# brain1_v12.net
KiCad netlist of a schematic drawn in EAGLE
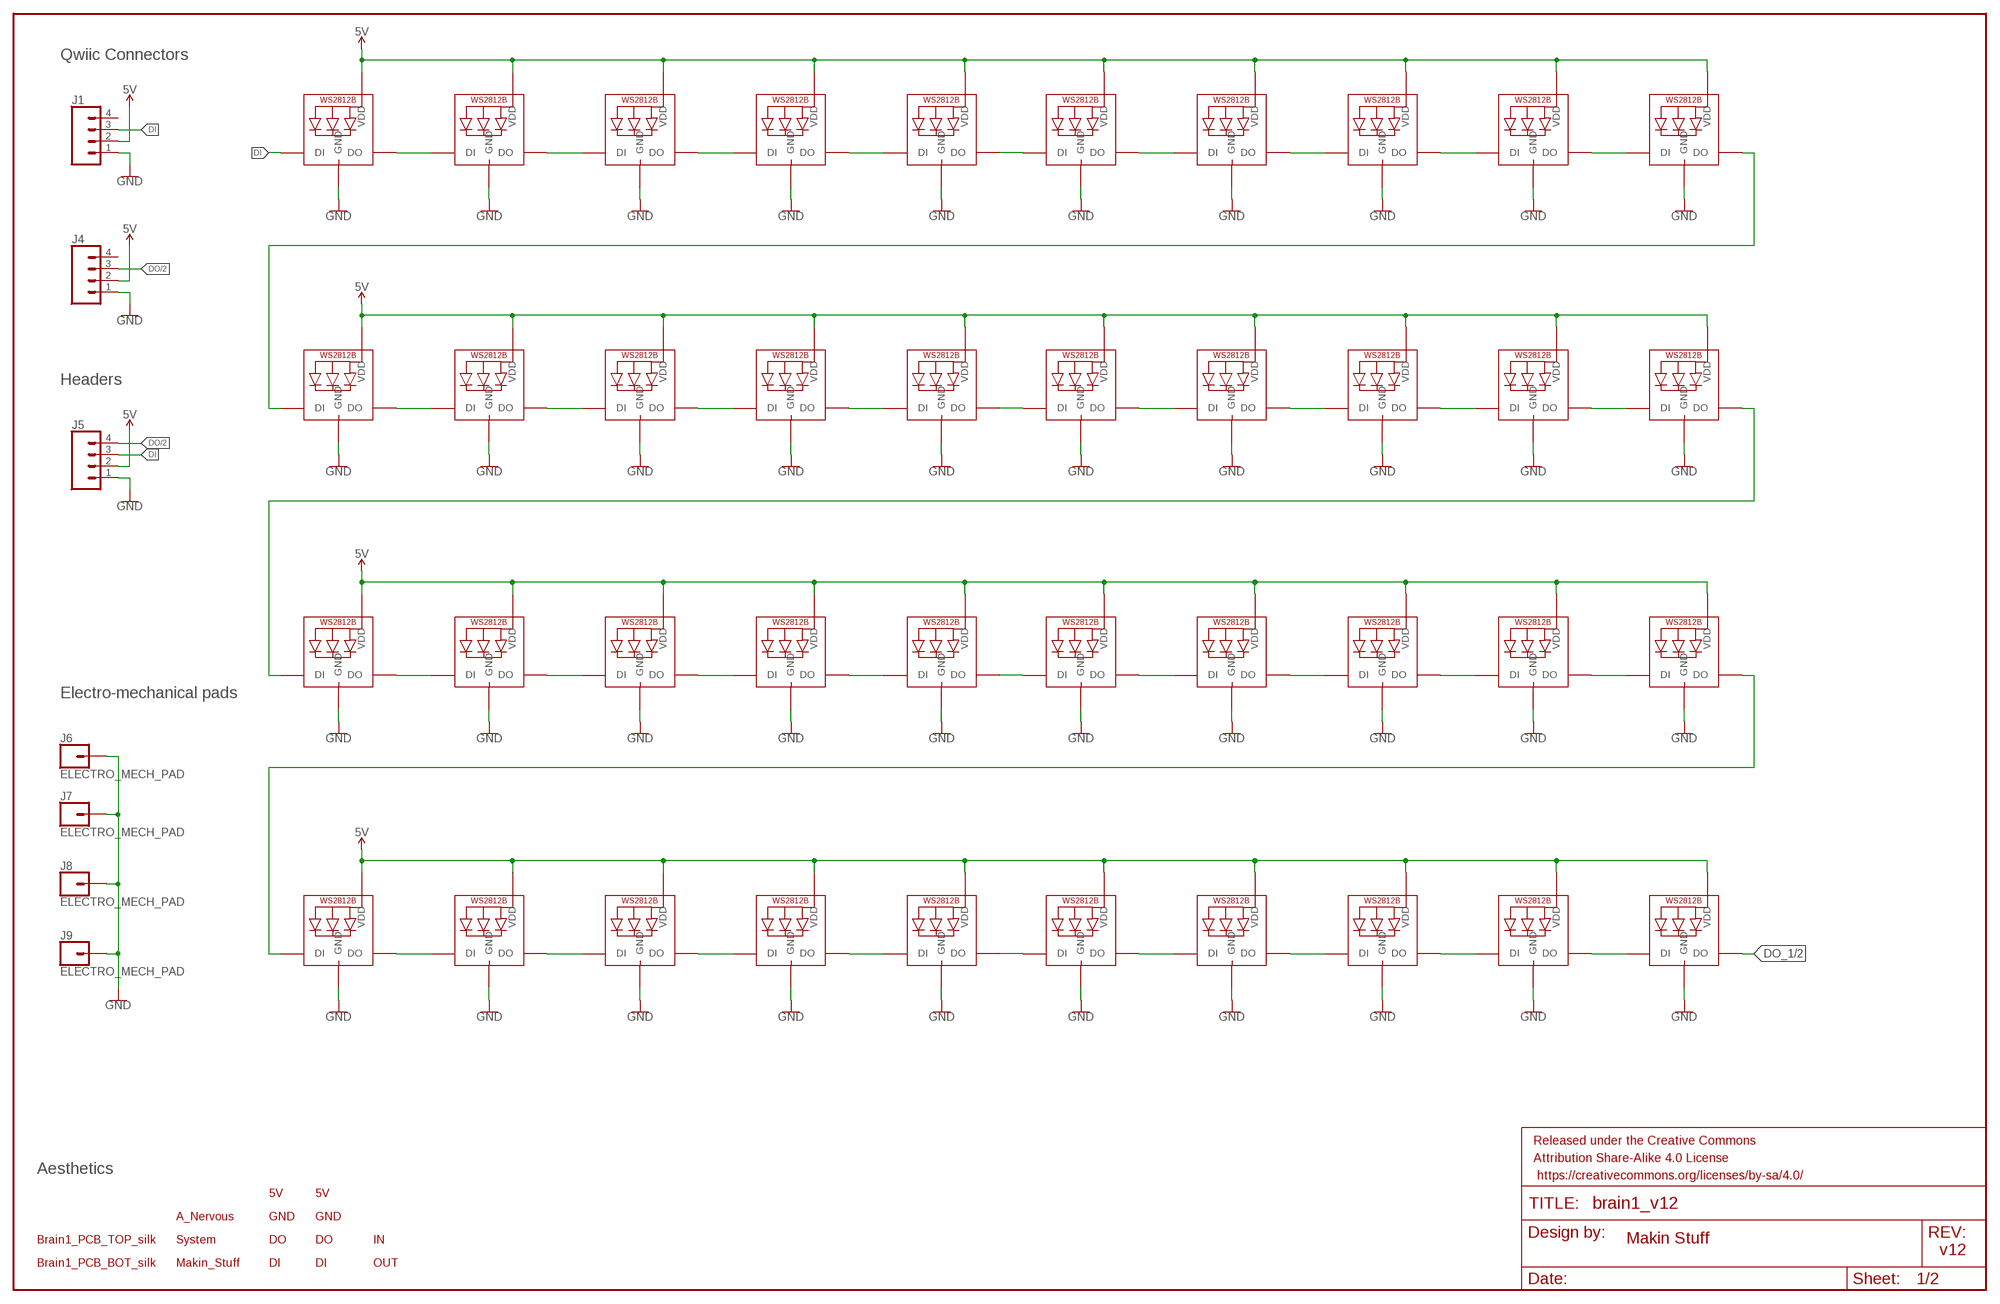
[diagram p0: schematic, sheet 1]
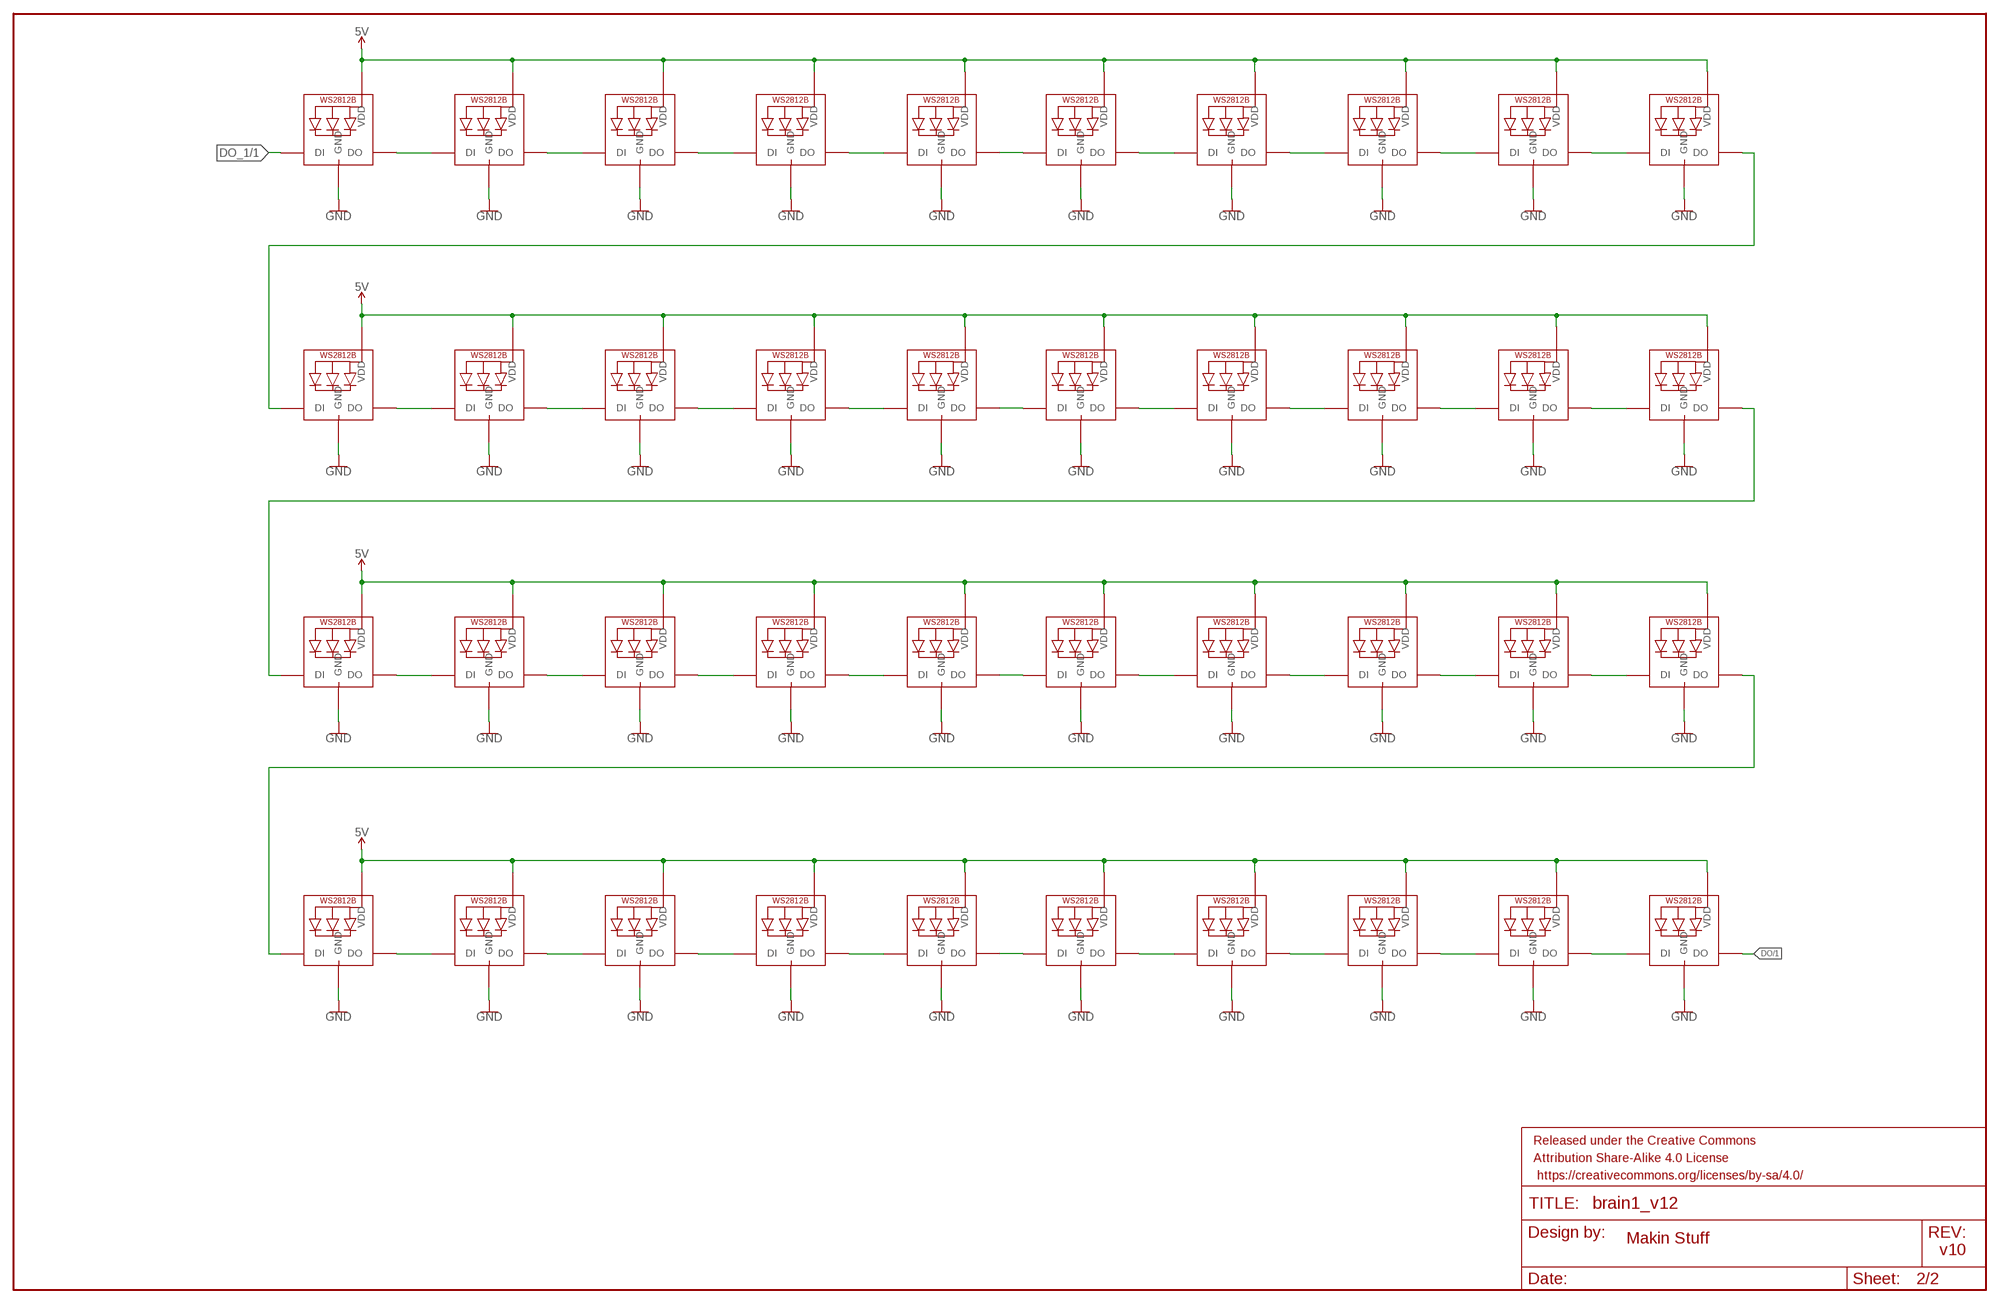
[diagram p1: schematic, sheet 2]

(export (version "E")
  (design (tool "Eeschema 10.0.6"))
  (components
    (comp (ref "FRAME1")
      (value "FRAME-LEDGER")
      (footprint "eagle-import:CREATIVE_COMMONS")
      (libsource (lib "eagle-import") (part "FRAME-LEDGER"))
    )
    (comp (ref "FRAME3")
      (value "FRAME-LEDGER")
      (footprint "eagle-import:CREATIVE_COMMONS")
      (libsource (lib "eagle-import") (part "FRAME-LEDGER"))
    )
    (comp (ref "LED41")
      (value "3.5X3.5_RGB_LED3.5X3.5")
      (footprint "eagle-import:3.5X3.5_RGB_LED")
      (libsource (lib "eagle-import") (part "3.5X3.5_RGB_LED3.5X3.5"))
    )
    (comp (ref "LED42")
      (value "3.5X3.5_RGB_LED3.5X3.5")
      (footprint "eagle-import:3.5X3.5_RGB_LED")
      (libsource (lib "eagle-import") (part "3.5X3.5_RGB_LED3.5X3.5"))
    )
    (comp (ref "LED43")
      (value "3.5X3.5_RGB_LED3.5X3.5")
      (footprint "eagle-import:3.5X3.5_RGB_LED")
      (libsource (lib "eagle-import") (part "3.5X3.5_RGB_LED3.5X3.5"))
    )
    (comp (ref "LED44")
      (value "3.5X3.5_RGB_LED3.5X3.5")
      (footprint "eagle-import:3.5X3.5_RGB_LED")
      (libsource (lib "eagle-import") (part "3.5X3.5_RGB_LED3.5X3.5"))
    )
    (comp (ref "LED45")
      (value "3.5X3.5_RGB_LED3.5X3.5")
      (footprint "eagle-import:3.5X3.5_RGB_LED")
      (libsource (lib "eagle-import") (part "3.5X3.5_RGB_LED3.5X3.5"))
    )
    (comp (ref "LED46")
      (value "3.5X3.5_RGB_LED3.5X3.5")
      (footprint "eagle-import:3.5X3.5_RGB_LED")
      (libsource (lib "eagle-import") (part "3.5X3.5_RGB_LED3.5X3.5"))
    )
    (comp (ref "LED47")
      (value "3.5X3.5_RGB_LED3.5X3.5")
      (footprint "eagle-import:3.5X3.5_RGB_LED")
      (libsource (lib "eagle-import") (part "3.5X3.5_RGB_LED3.5X3.5"))
    )
    (comp (ref "LED48")
      (value "3.5X3.5_RGB_LED3.5X3.5")
      (footprint "eagle-import:3.5X3.5_RGB_LED")
      (libsource (lib "eagle-import") (part "3.5X3.5_RGB_LED3.5X3.5"))
    )
    (comp (ref "LED49")
      (value "3.5X3.5_RGB_LED3.5X3.5")
      (footprint "eagle-import:3.5X3.5_RGB_LED")
      (libsource (lib "eagle-import") (part "3.5X3.5_RGB_LED3.5X3.5"))
    )
    (comp (ref "LED50")
      (value "3.5X3.5_RGB_LED3.5X3.5")
      (footprint "eagle-import:3.5X3.5_RGB_LED")
      (libsource (lib "eagle-import") (part "3.5X3.5_RGB_LED3.5X3.5"))
    )
    (comp (ref "LED51")
      (value "3.5X3.5_RGB_LED3.5X3.5")
      (footprint "eagle-import:3.5X3.5_RGB_LED")
      (libsource (lib "eagle-import") (part "3.5X3.5_RGB_LED3.5X3.5"))
    )
    (comp (ref "LED52")
      (value "3.5X3.5_RGB_LED3.5X3.5")
      (footprint "eagle-import:3.5X3.5_RGB_LED")
      (libsource (lib "eagle-import") (part "3.5X3.5_RGB_LED3.5X3.5"))
    )
    (comp (ref "LED53")
      (value "3.5X3.5_RGB_LED3.5X3.5")
      (footprint "eagle-import:3.5X3.5_RGB_LED")
      (libsource (lib "eagle-import") (part "3.5X3.5_RGB_LED3.5X3.5"))
    )
    (comp (ref "LED54")
      (value "3.5X3.5_RGB_LED3.5X3.5")
      (footprint "eagle-import:3.5X3.5_RGB_LED")
      (libsource (lib "eagle-import") (part "3.5X3.5_RGB_LED3.5X3.5"))
    )
    (comp (ref "LED55")
      (value "3.5X3.5_RGB_LED3.5X3.5")
      (footprint "eagle-import:3.5X3.5_RGB_LED")
      (libsource (lib "eagle-import") (part "3.5X3.5_RGB_LED3.5X3.5"))
    )
    (comp (ref "LED56")
      (value "3.5X3.5_RGB_LED3.5X3.5")
      (footprint "eagle-import:3.5X3.5_RGB_LED")
      (libsource (lib "eagle-import") (part "3.5X3.5_RGB_LED3.5X3.5"))
    )
    (comp (ref "LED57")
      (value "3.5X3.5_RGB_LED3.5X3.5")
      (footprint "eagle-import:3.5X3.5_RGB_LED")
      (libsource (lib "eagle-import") (part "3.5X3.5_RGB_LED3.5X3.5"))
    )
    (comp (ref "LED58")
      (value "3.5X3.5_RGB_LED3.5X3.5")
      (footprint "eagle-import:3.5X3.5_RGB_LED")
      (libsource (lib "eagle-import") (part "3.5X3.5_RGB_LED3.5X3.5"))
    )
    (comp (ref "LED59")
      (value "3.5X3.5_RGB_LED3.5X3.5")
      (footprint "eagle-import:3.5X3.5_RGB_LED")
      (libsource (lib "eagle-import") (part "3.5X3.5_RGB_LED3.5X3.5"))
    )
    (comp (ref "LED60")
      (value "3.5X3.5_RGB_LED3.5X3.5")
      (footprint "eagle-import:3.5X3.5_RGB_LED")
      (libsource (lib "eagle-import") (part "3.5X3.5_RGB_LED3.5X3.5"))
    )
    (comp (ref "LED61")
      (value "3.5X3.5_RGB_LED3.5X3.5")
      (footprint "eagle-import:3.5X3.5_RGB_LED")
      (libsource (lib "eagle-import") (part "3.5X3.5_RGB_LED3.5X3.5"))
    )
    (comp (ref "LED62")
      (value "3.5X3.5_RGB_LED3.5X3.5")
      (footprint "eagle-import:3.5X3.5_RGB_LED")
      (libsource (lib "eagle-import") (part "3.5X3.5_RGB_LED3.5X3.5"))
    )
    (comp (ref "LED63")
      (value "3.5X3.5_RGB_LED3.5X3.5")
      (footprint "eagle-import:3.5X3.5_RGB_LED")
      (libsource (lib "eagle-import") (part "3.5X3.5_RGB_LED3.5X3.5"))
    )
    (comp (ref "LED64")
      (value "3.5X3.5_RGB_LED3.5X3.5")
      (footprint "eagle-import:3.5X3.5_RGB_LED")
      (libsource (lib "eagle-import") (part "3.5X3.5_RGB_LED3.5X3.5"))
    )
    (comp (ref "LED65")
      (value "3.5X3.5_RGB_LED3.5X3.5")
      (footprint "eagle-import:3.5X3.5_RGB_LED")
      (libsource (lib "eagle-import") (part "3.5X3.5_RGB_LED3.5X3.5"))
    )
    (comp (ref "LED66")
      (value "3.5X3.5_RGB_LED3.5X3.5")
      (footprint "eagle-import:3.5X3.5_RGB_LED")
      (libsource (lib "eagle-import") (part "3.5X3.5_RGB_LED3.5X3.5"))
    )
    (comp (ref "LED67")
      (value "3.5X3.5_RGB_LED3.5X3.5")
      (footprint "eagle-import:3.5X3.5_RGB_LED")
      (libsource (lib "eagle-import") (part "3.5X3.5_RGB_LED3.5X3.5"))
    )
    (comp (ref "LED68")
      (value "3.5X3.5_RGB_LED3.5X3.5")
      (footprint "eagle-import:3.5X3.5_RGB_LED")
      (libsource (lib "eagle-import") (part "3.5X3.5_RGB_LED3.5X3.5"))
    )
    (comp (ref "LED69")
      (value "3.5X3.5_RGB_LED3.5X3.5")
      (footprint "eagle-import:3.5X3.5_RGB_LED")
      (libsource (lib "eagle-import") (part "3.5X3.5_RGB_LED3.5X3.5"))
    )
    (comp (ref "LED70")
      (value "3.5X3.5_RGB_LED3.5X3.5")
      (footprint "eagle-import:3.5X3.5_RGB_LED")
      (libsource (lib "eagle-import") (part "3.5X3.5_RGB_LED3.5X3.5"))
    )
    (comp (ref "LED71")
      (value "3.5X3.5_RGB_LED3.5X3.5")
      (footprint "eagle-import:3.5X3.5_RGB_LED")
      (libsource (lib "eagle-import") (part "3.5X3.5_RGB_LED3.5X3.5"))
    )
    (comp (ref "LED72")
      (value "3.5X3.5_RGB_LED3.5X3.5")
      (footprint "eagle-import:3.5X3.5_RGB_LED")
      (libsource (lib "eagle-import") (part "3.5X3.5_RGB_LED3.5X3.5"))
    )
    (comp (ref "LED73")
      (value "3.5X3.5_RGB_LED3.5X3.5")
      (footprint "eagle-import:3.5X3.5_RGB_LED")
      (libsource (lib "eagle-import") (part "3.5X3.5_RGB_LED3.5X3.5"))
    )
    (comp (ref "LED74")
      (value "3.5X3.5_RGB_LED3.5X3.5")
      (footprint "eagle-import:3.5X3.5_RGB_LED")
      (libsource (lib "eagle-import") (part "3.5X3.5_RGB_LED3.5X3.5"))
    )
    (comp (ref "LED75")
      (value "3.5X3.5_RGB_LED3.5X3.5")
      (footprint "eagle-import:3.5X3.5_RGB_LED")
      (libsource (lib "eagle-import") (part "3.5X3.5_RGB_LED3.5X3.5"))
    )
    (comp (ref "LED76")
      (value "3.5X3.5_RGB_LED3.5X3.5")
      (footprint "eagle-import:3.5X3.5_RGB_LED")
      (libsource (lib "eagle-import") (part "3.5X3.5_RGB_LED3.5X3.5"))
    )
    (comp (ref "LED77")
      (value "3.5X3.5_RGB_LED3.5X3.5")
      (footprint "eagle-import:3.5X3.5_RGB_LED")
      (libsource (lib "eagle-import") (part "3.5X3.5_RGB_LED3.5X3.5"))
    )
    (comp (ref "LED78")
      (value "3.5X3.5_RGB_LED3.5X3.5")
      (footprint "eagle-import:3.5X3.5_RGB_LED")
      (libsource (lib "eagle-import") (part "3.5X3.5_RGB_LED3.5X3.5"))
    )
    (comp (ref "LED79")
      (value "3.5X3.5_RGB_LED3.5X3.5")
      (footprint "eagle-import:3.5X3.5_RGB_LED")
      (libsource (lib "eagle-import") (part "3.5X3.5_RGB_LED3.5X3.5"))
    )
    (comp (ref "LED80")
      (value "3.5X3.5_RGB_LED3.5X3.5")
      (footprint "eagle-import:3.5X3.5_RGB_LED")
      (libsource (lib "eagle-import") (part "3.5X3.5_RGB_LED3.5X3.5"))
    )
    (comp (ref "FRAME2")
      (value "FRAME-LEDGER")
      (footprint "eagle-import:CREATIVE_COMMONS")
      (libsource (lib "eagle-import") (part "FRAME-LEDGER"))
    )
    (comp (ref "J1")
      (value "CONN_04SMD3")
      (footprint "eagle-import:JST04_1MM_RA")
      (libsource (lib "eagle-import") (part "CONN_04SMD3"))
    )
    (comp (ref "J4")
      (value "CONN_04SMD3")
      (footprint "eagle-import:JST04_1MM_RA")
      (libsource (lib "eagle-import") (part "CONN_04SMD3"))
    )
    (comp (ref "J5")
      (value "CONN_041X04_NO_SILK_NO_POP")
      (footprint "eagle-import:1X04_NO_SILK")
      (libsource (lib "eagle-import") (part "CONN_041X04_NO_SILK_NO_POP"))
    )
    (comp (ref "J6")
      (value "ELECTRO_MECH_PAD")
      (footprint "eagle-import:5X3_SOLDER_PAD")
      (libsource (lib "eagle-import") (part "ELECTRO_MECH_PAD"))
    )
    (comp (ref "J7")
      (value "ELECTRO_MECH_PAD")
      (footprint "eagle-import:5X3_SOLDER_PAD")
      (libsource (lib "eagle-import") (part "ELECTRO_MECH_PAD"))
    )
    (comp (ref "J8")
      (value "ELECTRO_MECH_PAD")
      (footprint "eagle-import:5X3_SOLDER_PAD")
      (libsource (lib "eagle-import") (part "ELECTRO_MECH_PAD"))
    )
    (comp (ref "J9")
      (value "ELECTRO_MECH_PAD")
      (footprint "eagle-import:5X3_SOLDER_PAD")
      (libsource (lib "eagle-import") (part "ELECTRO_MECH_PAD"))
    )
    (comp (ref "LED1")
      (value "3.5X3.5_RGB_LED3.5X3.5")
      (footprint "eagle-import:3.5X3.5_RGB_LED")
      (libsource (lib "eagle-import") (part "3.5X3.5_RGB_LED3.5X3.5"))
    )
    (comp (ref "LED2")
      (value "3.5X3.5_RGB_LED3.5X3.5")
      (footprint "eagle-import:3.5X3.5_RGB_LED")
      (libsource (lib "eagle-import") (part "3.5X3.5_RGB_LED3.5X3.5"))
    )
    (comp (ref "LED3")
      (value "3.5X3.5_RGB_LED3.5X3.5")
      (footprint "eagle-import:3.5X3.5_RGB_LED")
      (libsource (lib "eagle-import") (part "3.5X3.5_RGB_LED3.5X3.5"))
    )
    (comp (ref "LED4")
      (value "3.5X3.5_RGB_LED3.5X3.5")
      (footprint "eagle-import:3.5X3.5_RGB_LED")
      (libsource (lib "eagle-import") (part "3.5X3.5_RGB_LED3.5X3.5"))
    )
    (comp (ref "LED5")
      (value "3.5X3.5_RGB_LED3.5X3.5")
      (footprint "eagle-import:3.5X3.5_RGB_LED")
      (libsource (lib "eagle-import") (part "3.5X3.5_RGB_LED3.5X3.5"))
    )
    (comp (ref "LED6")
      (value "3.5X3.5_RGB_LED3.5X3.5")
      (footprint "eagle-import:3.5X3.5_RGB_LED")
      (libsource (lib "eagle-import") (part "3.5X3.5_RGB_LED3.5X3.5"))
    )
    (comp (ref "LED7")
      (value "3.5X3.5_RGB_LED3.5X3.5")
      (footprint "eagle-import:3.5X3.5_RGB_LED")
      (libsource (lib "eagle-import") (part "3.5X3.5_RGB_LED3.5X3.5"))
    )
    (comp (ref "LED8")
      (value "3.5X3.5_RGB_LED3.5X3.5")
      (footprint "eagle-import:3.5X3.5_RGB_LED")
      (libsource (lib "eagle-import") (part "3.5X3.5_RGB_LED3.5X3.5"))
    )
    (comp (ref "LED9")
      (value "3.5X3.5_RGB_LED3.5X3.5")
      (footprint "eagle-import:3.5X3.5_RGB_LED")
      (libsource (lib "eagle-import") (part "3.5X3.5_RGB_LED3.5X3.5"))
    )
    (comp (ref "LED10")
      (value "3.5X3.5_RGB_LED3.5X3.5")
      (footprint "eagle-import:3.5X3.5_RGB_LED")
      (libsource (lib "eagle-import") (part "3.5X3.5_RGB_LED3.5X3.5"))
    )
    (comp (ref "LED11")
      (value "3.5X3.5_RGB_LED3.5X3.5")
      (footprint "eagle-import:3.5X3.5_RGB_LED")
      (libsource (lib "eagle-import") (part "3.5X3.5_RGB_LED3.5X3.5"))
    )
    (comp (ref "LED12")
      (value "3.5X3.5_RGB_LED3.5X3.5")
      (footprint "eagle-import:3.5X3.5_RGB_LED")
      (libsource (lib "eagle-import") (part "3.5X3.5_RGB_LED3.5X3.5"))
    )
    (comp (ref "LED13")
      (value "3.5X3.5_RGB_LED3.5X3.5")
      (footprint "eagle-import:3.5X3.5_RGB_LED")
      (libsource (lib "eagle-import") (part "3.5X3.5_RGB_LED3.5X3.5"))
    )
    (comp (ref "LED14")
      (value "3.5X3.5_RGB_LED3.5X3.5")
      (footprint "eagle-import:3.5X3.5_RGB_LED")
      (libsource (lib "eagle-import") (part "3.5X3.5_RGB_LED3.5X3.5"))
    )
    (comp (ref "LED15")
      (value "3.5X3.5_RGB_LED3.5X3.5")
      (footprint "eagle-import:3.5X3.5_RGB_LED")
      (libsource (lib "eagle-import") (part "3.5X3.5_RGB_LED3.5X3.5"))
    )
    (comp (ref "LED16")
      (value "3.5X3.5_RGB_LED3.5X3.5")
      (footprint "eagle-import:3.5X3.5_RGB_LED")
      (libsource (lib "eagle-import") (part "3.5X3.5_RGB_LED3.5X3.5"))
    )
    (comp (ref "LED17")
      (value "3.5X3.5_RGB_LED3.5X3.5")
      (footprint "eagle-import:3.5X3.5_RGB_LED")
      (libsource (lib "eagle-import") (part "3.5X3.5_RGB_LED3.5X3.5"))
    )
    (comp (ref "LED18")
      (value "3.5X3.5_RGB_LED3.5X3.5")
      (footprint "eagle-import:3.5X3.5_RGB_LED")
      (libsource (lib "eagle-import") (part "3.5X3.5_RGB_LED3.5X3.5"))
    )
    (comp (ref "LED19")
      (value "3.5X3.5_RGB_LED3.5X3.5")
      (footprint "eagle-import:3.5X3.5_RGB_LED")
      (libsource (lib "eagle-import") (part "3.5X3.5_RGB_LED3.5X3.5"))
    )
    (comp (ref "LED20")
      (value "3.5X3.5_RGB_LED3.5X3.5")
      (footprint "eagle-import:3.5X3.5_RGB_LED")
      (libsource (lib "eagle-import") (part "3.5X3.5_RGB_LED3.5X3.5"))
    )
    (comp (ref "LED21")
      (value "3.5X3.5_RGB_LED3.5X3.5")
      (footprint "eagle-import:3.5X3.5_RGB_LED")
      (libsource (lib "eagle-import") (part "3.5X3.5_RGB_LED3.5X3.5"))
    )
    (comp (ref "LED22")
      (value "3.5X3.5_RGB_LED3.5X3.5")
      (footprint "eagle-import:3.5X3.5_RGB_LED")
      (libsource (lib "eagle-import") (part "3.5X3.5_RGB_LED3.5X3.5"))
    )
    (comp (ref "LED23")
      (value "3.5X3.5_RGB_LED3.5X3.5")
      (footprint "eagle-import:3.5X3.5_RGB_LED")
      (libsource (lib "eagle-import") (part "3.5X3.5_RGB_LED3.5X3.5"))
    )
    (comp (ref "LED24")
      (value "3.5X3.5_RGB_LED3.5X3.5")
      (footprint "eagle-import:3.5X3.5_RGB_LED")
      (libsource (lib "eagle-import") (part "3.5X3.5_RGB_LED3.5X3.5"))
    )
    (comp (ref "LED25")
      (value "3.5X3.5_RGB_LED3.5X3.5")
      (footprint "eagle-import:3.5X3.5_RGB_LED")
      (libsource (lib "eagle-import") (part "3.5X3.5_RGB_LED3.5X3.5"))
    )
    (comp (ref "LED26")
      (value "3.5X3.5_RGB_LED3.5X3.5")
      (footprint "eagle-import:3.5X3.5_RGB_LED")
      (libsource (lib "eagle-import") (part "3.5X3.5_RGB_LED3.5X3.5"))
    )
    (comp (ref "LED27")
      (value "3.5X3.5_RGB_LED3.5X3.5")
      (footprint "eagle-import:3.5X3.5_RGB_LED")
      (libsource (lib "eagle-import") (part "3.5X3.5_RGB_LED3.5X3.5"))
    )
    (comp (ref "LED28")
      (value "3.5X3.5_RGB_LED3.5X3.5")
      (footprint "eagle-import:3.5X3.5_RGB_LED")
      (libsource (lib "eagle-import") (part "3.5X3.5_RGB_LED3.5X3.5"))
    )
    (comp (ref "LED29")
      (value "3.5X3.5_RGB_LED3.5X3.5")
      (footprint "eagle-import:3.5X3.5_RGB_LED")
      (libsource (lib "eagle-import") (part "3.5X3.5_RGB_LED3.5X3.5"))
    )
    (comp (ref "LED30")
      (value "3.5X3.5_RGB_LED3.5X3.5")
      (footprint "eagle-import:3.5X3.5_RGB_LED")
      (libsource (lib "eagle-import") (part "3.5X3.5_RGB_LED3.5X3.5"))
    )
    (comp (ref "LED31")
      (value "3.5X3.5_RGB_LED3.5X3.5")
      (footprint "eagle-import:3.5X3.5_RGB_LED")
      (libsource (lib "eagle-import") (part "3.5X3.5_RGB_LED3.5X3.5"))
    )
    (comp (ref "LED32")
      (value "3.5X3.5_RGB_LED3.5X3.5")
      (footprint "eagle-import:3.5X3.5_RGB_LED")
      (libsource (lib "eagle-import") (part "3.5X3.5_RGB_LED3.5X3.5"))
    )
    (comp (ref "LED33")
      (value "3.5X3.5_RGB_LED3.5X3.5")
      (footprint "eagle-import:3.5X3.5_RGB_LED")
      (libsource (lib "eagle-import") (part "3.5X3.5_RGB_LED3.5X3.5"))
    )
    (comp (ref "LED34")
      (value "3.5X3.5_RGB_LED3.5X3.5")
      (footprint "eagle-import:3.5X3.5_RGB_LED")
      (libsource (lib "eagle-import") (part "3.5X3.5_RGB_LED3.5X3.5"))
    )
    (comp (ref "LED35")
      (value "3.5X3.5_RGB_LED3.5X3.5")
      (footprint "eagle-import:3.5X3.5_RGB_LED")
      (libsource (lib "eagle-import") (part "3.5X3.5_RGB_LED3.5X3.5"))
    )
    (comp (ref "LED36")
      (value "3.5X3.5_RGB_LED3.5X3.5")
      (footprint "eagle-import:3.5X3.5_RGB_LED")
      (libsource (lib "eagle-import") (part "3.5X3.5_RGB_LED3.5X3.5"))
    )
    (comp (ref "LED37")
      (value "3.5X3.5_RGB_LED3.5X3.5")
      (footprint "eagle-import:3.5X3.5_RGB_LED")
      (libsource (lib "eagle-import") (part "3.5X3.5_RGB_LED3.5X3.5"))
    )
    (comp (ref "LED38")
      (value "3.5X3.5_RGB_LED3.5X3.5")
      (footprint "eagle-import:3.5X3.5_RGB_LED")
      (libsource (lib "eagle-import") (part "3.5X3.5_RGB_LED3.5X3.5"))
    )
    (comp (ref "LED39")
      (value "3.5X3.5_RGB_LED3.5X3.5")
      (footprint "eagle-import:3.5X3.5_RGB_LED")
      (libsource (lib "eagle-import") (part "3.5X3.5_RGB_LED3.5X3.5"))
    )
    (comp (ref "LED40")
      (value "3.5X3.5_RGB_LED3.5X3.5")
      (footprint "eagle-import:3.5X3.5_RGB_LED")
      (libsource (lib "eagle-import") (part "3.5X3.5_RGB_LED3.5X3.5"))
    )
    (comp (ref "U$1")
      (value "BRAIN1_PCB_BOT_SILK")
      (footprint "eagle-import:BRAIN1_PCB_BOT_SILK")
      (libsource (lib "eagle-import") (part "BRAIN1_PCB_BOT_SILK"))
    )
    (comp (ref "U$2")
      (value "BRAIN1_PCB_TOP_SILK")
      (footprint "eagle-import:BRAIN1_PCB_TOP_SILK")
      (libsource (lib "eagle-import") (part "BRAIN1_PCB_TOP_SILK"))
    )
    (comp (ref "U$3")
      (value "MAKIN_STUFF2")
      (footprint "eagle-import:MAKIN_STUFF2")
      (libsource (lib "eagle-import") (part "MAKIN_STUFF2"))
    )
    (comp (ref "U$4")
      (value "A_NERVOUS0")
      (footprint "eagle-import:A_NERVOUS0")
      (libsource (lib "eagle-import") (part "A_NERVOUS0"))
    )
    (comp (ref "U$5")
      (value "SYSTEM1")
      (footprint "eagle-import:SYSTEM1")
      (libsource (lib "eagle-import") (part "SYSTEM1"))
    )
    (comp (ref "U$6")
      (value "5V1")
      (footprint "eagle-import:5V1")
      (libsource (lib "eagle-import") (part "buzzard_labels (6)_5V1"))
    )
    (comp (ref "U$7")
      (value "GND0")
      (footprint "eagle-import:GND0")
      (libsource (lib "eagle-import") (part "buzzard_labels (6)_GND0"))
    )
    (comp (ref "U$8")
      (value "DO3")
      (footprint "eagle-import:DO3")
      (libsource (lib "eagle-import") (part "buzzard_labels (6)_DO3"))
    )
    (comp (ref "U$9")
      (value "DI0")
      (footprint "eagle-import:DI0")
      (libsource (lib "eagle-import") (part "buzzard_labels (7)_DI0"))
    )
    (comp (ref "U$10")
      (value "5V1")
      (footprint "eagle-import:5V1")
      (libsource (lib "eagle-import") (part "5V1"))
    )
    (comp (ref "U$11")
      (value "GND0")
      (footprint "eagle-import:GND0")
      (libsource (lib "eagle-import") (part "GND0"))
    )
    (comp (ref "U$12")
      (value "DI0")
      (footprint "eagle-import:DI0")
      (libsource (lib "eagle-import") (part "DI0"))
    )
    (comp (ref "U$13")
      (value "DO3")
      (footprint "eagle-import:DO3")
      (libsource (lib "eagle-import") (part "DO3"))
    )
    (comp (ref "U$14")
      (value "IN0")
      (footprint "eagle-import:IN0")
      (libsource (lib "eagle-import") (part "IN0"))
    )
    (comp (ref "U$15")
      (value "OUT1")
      (footprint "eagle-import:OUT1")
      (libsource (lib "eagle-import") (part "OUT1"))
    )
  )
  (nets
    (net (code "1") (name "5V") (class "Default")
      (node (ref "J1") (pin "2") (pinfunction "2_2") (pintype "passive"))
      (node (ref "J4") (pin "2") (pinfunction "2_2") (pintype "passive"))
      (node (ref "J5") (pin "2") (pinfunction "2_2") (pintype "passive"))
      (node (ref "LED1") (pin "4") (pinfunction "VDD_4") (pintype "power_in"))
      (node (ref "LED10") (pin "4") (pinfunction "VDD_4") (pintype "power_in"))
      (node (ref "LED11") (pin "4") (pinfunction "VDD_4") (pintype "power_in"))
      (node (ref "LED12") (pin "4") (pinfunction "VDD_4") (pintype "power_in"))
      (node (ref "LED13") (pin "4") (pinfunction "VDD_4") (pintype "power_in"))
      (node (ref "LED14") (pin "4") (pinfunction "VDD_4") (pintype "power_in"))
      (node (ref "LED15") (pin "4") (pinfunction "VDD_4") (pintype "power_in"))
      (node (ref "LED16") (pin "4") (pinfunction "VDD_4") (pintype "power_in"))
      (node (ref "LED17") (pin "4") (pinfunction "VDD_4") (pintype "power_in"))
      (node (ref "LED18") (pin "4") (pinfunction "VDD_4") (pintype "power_in"))
      (node (ref "LED19") (pin "4") (pinfunction "VDD_4") (pintype "power_in"))
      (node (ref "LED2") (pin "4") (pinfunction "VDD_4") (pintype "power_in"))
      (node (ref "LED20") (pin "4") (pinfunction "VDD_4") (pintype "power_in"))
      (node (ref "LED21") (pin "4") (pinfunction "VDD_4") (pintype "power_in"))
      (node (ref "LED22") (pin "4") (pinfunction "VDD_4") (pintype "power_in"))
      (node (ref "LED23") (pin "4") (pinfunction "VDD_4") (pintype "power_in"))
      (node (ref "LED24") (pin "4") (pinfunction "VDD_4") (pintype "power_in"))
      (node (ref "LED25") (pin "4") (pinfunction "VDD_4") (pintype "power_in"))
      (node (ref "LED26") (pin "4") (pinfunction "VDD_4") (pintype "power_in"))
      (node (ref "LED27") (pin "4") (pinfunction "VDD_4") (pintype "power_in"))
      (node (ref "LED28") (pin "4") (pinfunction "VDD_4") (pintype "power_in"))
      (node (ref "LED29") (pin "4") (pinfunction "VDD_4") (pintype "power_in"))
      (node (ref "LED3") (pin "4") (pinfunction "VDD_4") (pintype "power_in"))
      (node (ref "LED30") (pin "4") (pinfunction "VDD_4") (pintype "power_in"))
      (node (ref "LED31") (pin "4") (pinfunction "VDD_4") (pintype "power_in"))
      (node (ref "LED32") (pin "4") (pinfunction "VDD_4") (pintype "power_in"))
      (node (ref "LED33") (pin "4") (pinfunction "VDD_4") (pintype "power_in"))
      (node (ref "LED34") (pin "4") (pinfunction "VDD_4") (pintype "power_in"))
      (node (ref "LED35") (pin "4") (pinfunction "VDD_4") (pintype "power_in"))
      (node (ref "LED36") (pin "4") (pinfunction "VDD_4") (pintype "power_in"))
      (node (ref "LED37") (pin "4") (pinfunction "VDD_4") (pintype "power_in"))
      (node (ref "LED38") (pin "4") (pinfunction "VDD_4") (pintype "power_in"))
      (node (ref "LED39") (pin "4") (pinfunction "VDD_4") (pintype "power_in"))
      (node (ref "LED4") (pin "4") (pinfunction "VDD_4") (pintype "power_in"))
      (node (ref "LED40") (pin "4") (pinfunction "VDD_4") (pintype "power_in"))
      (node (ref "LED41") (pin "4") (pinfunction "VDD_4") (pintype "power_in"))
      (node (ref "LED42") (pin "4") (pinfunction "VDD_4") (pintype "power_in"))
      (node (ref "LED43") (pin "4") (pinfunction "VDD_4") (pintype "power_in"))
      (node (ref "LED44") (pin "4") (pinfunction "VDD_4") (pintype "power_in"))
      (node (ref "LED45") (pin "4") (pinfunction "VDD_4") (pintype "power_in"))
      (node (ref "LED46") (pin "4") (pinfunction "VDD_4") (pintype "power_in"))
      (node (ref "LED47") (pin "4") (pinfunction "VDD_4") (pintype "power_in"))
      (node (ref "LED48") (pin "4") (pinfunction "VDD_4") (pintype "power_in"))
      (node (ref "LED49") (pin "4") (pinfunction "VDD_4") (pintype "power_in"))
      (node (ref "LED5") (pin "4") (pinfunction "VDD_4") (pintype "power_in"))
      (node (ref "LED50") (pin "4") (pinfunction "VDD_4") (pintype "power_in"))
      (node (ref "LED51") (pin "4") (pinfunction "VDD_4") (pintype "power_in"))
      (node (ref "LED52") (pin "4") (pinfunction "VDD_4") (pintype "power_in"))
      (node (ref "LED53") (pin "4") (pinfunction "VDD_4") (pintype "power_in"))
      (node (ref "LED54") (pin "4") (pinfunction "VDD_4") (pintype "power_in"))
      (node (ref "LED55") (pin "4") (pinfunction "VDD_4") (pintype "power_in"))
      (node (ref "LED56") (pin "4") (pinfunction "VDD_4") (pintype "power_in"))
      (node (ref "LED57") (pin "4") (pinfunction "VDD_4") (pintype "power_in"))
      (node (ref "LED58") (pin "4") (pinfunction "VDD_4") (pintype "power_in"))
      (node (ref "LED59") (pin "4") (pinfunction "VDD_4") (pintype "power_in"))
      (node (ref "LED6") (pin "4") (pinfunction "VDD_4") (pintype "power_in"))
      (node (ref "LED60") (pin "4") (pinfunction "VDD_4") (pintype "power_in"))
      (node (ref "LED61") (pin "4") (pinfunction "VDD_4") (pintype "power_in"))
      (node (ref "LED62") (pin "4") (pinfunction "VDD_4") (pintype "power_in"))
      (node (ref "LED63") (pin "4") (pinfunction "VDD_4") (pintype "power_in"))
      (node (ref "LED64") (pin "4") (pinfunction "VDD_4") (pintype "power_in"))
      (node (ref "LED65") (pin "4") (pinfunction "VDD_4") (pintype "power_in"))
      (node (ref "LED66") (pin "4") (pinfunction "VDD_4") (pintype "power_in"))
      (node (ref "LED67") (pin "4") (pinfunction "VDD_4") (pintype "power_in"))
      (node (ref "LED68") (pin "4") (pinfunction "VDD_4") (pintype "power_in"))
      (node (ref "LED69") (pin "4") (pinfunction "VDD_4") (pintype "power_in"))
      (node (ref "LED7") (pin "4") (pinfunction "VDD_4") (pintype "power_in"))
      (node (ref "LED70") (pin "4") (pinfunction "VDD_4") (pintype "power_in"))
      (node (ref "LED71") (pin "4") (pinfunction "VDD_4") (pintype "power_in"))
      (node (ref "LED72") (pin "4") (pinfunction "VDD_4") (pintype "power_in"))
      (node (ref "LED73") (pin "4") (pinfunction "VDD_4") (pintype "power_in"))
      (node (ref "LED74") (pin "4") (pinfunction "VDD_4") (pintype "power_in"))
      (node (ref "LED75") (pin "4") (pinfunction "VDD_4") (pintype "power_in"))
      (node (ref "LED76") (pin "4") (pinfunction "VDD_4") (pintype "power_in"))
      (node (ref "LED77") (pin "4") (pinfunction "VDD_4") (pintype "power_in"))
      (node (ref "LED78") (pin "4") (pinfunction "VDD_4") (pintype "power_in"))
      (node (ref "LED79") (pin "4") (pinfunction "VDD_4") (pintype "power_in"))
      (node (ref "LED8") (pin "4") (pinfunction "VDD_4") (pintype "power_in"))
      (node (ref "LED80") (pin "4") (pinfunction "VDD_4") (pintype "power_in"))
      (node (ref "LED9") (pin "4") (pinfunction "VDD_4") (pintype "power_in"))
    )
    (net (code "2") (name "DI") (class "Default")
      (node (ref "J1") (pin "3") (pinfunction "3_3") (pintype "passive"))
      (node (ref "J5") (pin "3") (pinfunction "3_3") (pintype "passive"))
      (node (ref "LED1") (pin "3") (pinfunction "DI_3") (pintype "input"))
    )
    (net (code "3") (name "DO") (class "Default")
      (node (ref "J4") (pin "3") (pinfunction "3_3") (pintype "passive"))
      (node (ref "J5") (pin "4") (pinfunction "4_4") (pintype "passive"))
      (node (ref "LED80") (pin "1") (pinfunction "DO_1") (pintype "output"))
    )
    (net (code "4") (name "DO_1") (class "Default")
      (node (ref "LED40") (pin "1") (pinfunction "DO_1") (pintype "output"))
      (node (ref "LED41") (pin "3") (pinfunction "DI_3") (pintype "input"))
    )
    (net (code "5") (name "GND") (class "Default")
      (node (ref "J1") (pin "1") (pinfunction "1_1") (pintype "passive"))
      (node (ref "J4") (pin "1") (pinfunction "1_1") (pintype "passive"))
      (node (ref "J5") (pin "1") (pinfunction "1_1") (pintype "passive"))
      (node (ref "J6") (pin "P$1") (pinfunction "1_P$1") (pintype "passive"))
      (node (ref "J7") (pin "P$1") (pinfunction "1_P$1") (pintype "passive"))
      (node (ref "J8") (pin "P$1") (pinfunction "1_P$1") (pintype "passive"))
      (node (ref "J9") (pin "P$1") (pinfunction "1_P$1") (pintype "passive"))
      (node (ref "LED1") (pin "2") (pinfunction "GND_2") (pintype "power_in"))
      (node (ref "LED10") (pin "2") (pinfunction "GND_2") (pintype "power_in"))
      (node (ref "LED11") (pin "2") (pinfunction "GND_2") (pintype "power_in"))
      (node (ref "LED12") (pin "2") (pinfunction "GND_2") (pintype "power_in"))
      (node (ref "LED13") (pin "2") (pinfunction "GND_2") (pintype "power_in"))
      (node (ref "LED14") (pin "2") (pinfunction "GND_2") (pintype "power_in"))
      (node (ref "LED15") (pin "2") (pinfunction "GND_2") (pintype "power_in"))
      (node (ref "LED16") (pin "2") (pinfunction "GND_2") (pintype "power_in"))
      (node (ref "LED17") (pin "2") (pinfunction "GND_2") (pintype "power_in"))
      (node (ref "LED18") (pin "2") (pinfunction "GND_2") (pintype "power_in"))
      (node (ref "LED19") (pin "2") (pinfunction "GND_2") (pintype "power_in"))
      (node (ref "LED2") (pin "2") (pinfunction "GND_2") (pintype "power_in"))
      (node (ref "LED20") (pin "2") (pinfunction "GND_2") (pintype "power_in"))
      (node (ref "LED21") (pin "2") (pinfunction "GND_2") (pintype "power_in"))
      (node (ref "LED22") (pin "2") (pinfunction "GND_2") (pintype "power_in"))
      (node (ref "LED23") (pin "2") (pinfunction "GND_2") (pintype "power_in"))
      (node (ref "LED24") (pin "2") (pinfunction "GND_2") (pintype "power_in"))
      (node (ref "LED25") (pin "2") (pinfunction "GND_2") (pintype "power_in"))
      (node (ref "LED26") (pin "2") (pinfunction "GND_2") (pintype "power_in"))
      (node (ref "LED27") (pin "2") (pinfunction "GND_2") (pintype "power_in"))
      (node (ref "LED28") (pin "2") (pinfunction "GND_2") (pintype "power_in"))
      (node (ref "LED29") (pin "2") (pinfunction "GND_2") (pintype "power_in"))
      (node (ref "LED3") (pin "2") (pinfunction "GND_2") (pintype "power_in"))
      (node (ref "LED30") (pin "2") (pinfunction "GND_2") (pintype "power_in"))
      (node (ref "LED31") (pin "2") (pinfunction "GND_2") (pintype "power_in"))
      (node (ref "LED32") (pin "2") (pinfunction "GND_2") (pintype "power_in"))
      (node (ref "LED33") (pin "2") (pinfunction "GND_2") (pintype "power_in"))
      (node (ref "LED34") (pin "2") (pinfunction "GND_2") (pintype "power_in"))
      (node (ref "LED35") (pin "2") (pinfunction "GND_2") (pintype "power_in"))
      (node (ref "LED36") (pin "2") (pinfunction "GND_2") (pintype "power_in"))
      (node (ref "LED37") (pin "2") (pinfunction "GND_2") (pintype "power_in"))
      (node (ref "LED38") (pin "2") (pinfunction "GND_2") (pintype "power_in"))
      (node (ref "LED39") (pin "2") (pinfunction "GND_2") (pintype "power_in"))
      (node (ref "LED4") (pin "2") (pinfunction "GND_2") (pintype "power_in"))
      (node (ref "LED40") (pin "2") (pinfunction "GND_2") (pintype "power_in"))
      (node (ref "LED41") (pin "2") (pinfunction "GND_2") (pintype "power_in"))
      (node (ref "LED42") (pin "2") (pinfunction "GND_2") (pintype "power_in"))
      (node (ref "LED43") (pin "2") (pinfunction "GND_2") (pintype "power_in"))
      (node (ref "LED44") (pin "2") (pinfunction "GND_2") (pintype "power_in"))
      (node (ref "LED45") (pin "2") (pinfunction "GND_2") (pintype "power_in"))
      (node (ref "LED46") (pin "2") (pinfunction "GND_2") (pintype "power_in"))
      (node (ref "LED47") (pin "2") (pinfunction "GND_2") (pintype "power_in"))
      (node (ref "LED48") (pin "2") (pinfunction "GND_2") (pintype "power_in"))
      (node (ref "LED49") (pin "2") (pinfunction "GND_2") (pintype "power_in"))
      (node (ref "LED5") (pin "2") (pinfunction "GND_2") (pintype "power_in"))
      (node (ref "LED50") (pin "2") (pinfunction "GND_2") (pintype "power_in"))
      (node (ref "LED51") (pin "2") (pinfunction "GND_2") (pintype "power_in"))
      (node (ref "LED52") (pin "2") (pinfunction "GND_2") (pintype "power_in"))
      (node (ref "LED53") (pin "2") (pinfunction "GND_2") (pintype "power_in"))
      (node (ref "LED54") (pin "2") (pinfunction "GND_2") (pintype "power_in"))
      (node (ref "LED55") (pin "2") (pinfunction "GND_2") (pintype "power_in"))
      (node (ref "LED56") (pin "2") (pinfunction "GND_2") (pintype "power_in"))
      (node (ref "LED57") (pin "2") (pinfunction "GND_2") (pintype "power_in"))
      (node (ref "LED58") (pin "2") (pinfunction "GND_2") (pintype "power_in"))
      (node (ref "LED59") (pin "2") (pinfunction "GND_2") (pintype "power_in"))
      (node (ref "LED6") (pin "2") (pinfunction "GND_2") (pintype "power_in"))
      (node (ref "LED60") (pin "2") (pinfunction "GND_2") (pintype "power_in"))
      (node (ref "LED61") (pin "2") (pinfunction "GND_2") (pintype "power_in"))
      (node (ref "LED62") (pin "2") (pinfunction "GND_2") (pintype "power_in"))
      (node (ref "LED63") (pin "2") (pinfunction "GND_2") (pintype "power_in"))
      (node (ref "LED64") (pin "2") (pinfunction "GND_2") (pintype "power_in"))
      (node (ref "LED65") (pin "2") (pinfunction "GND_2") (pintype "power_in"))
      (node (ref "LED66") (pin "2") (pinfunction "GND_2") (pintype "power_in"))
      (node (ref "LED67") (pin "2") (pinfunction "GND_2") (pintype "power_in"))
      (node (ref "LED68") (pin "2") (pinfunction "GND_2") (pintype "power_in"))
      (node (ref "LED69") (pin "2") (pinfunction "GND_2") (pintype "power_in"))
      (node (ref "LED7") (pin "2") (pinfunction "GND_2") (pintype "power_in"))
      (node (ref "LED70") (pin "2") (pinfunction "GND_2") (pintype "power_in"))
      (node (ref "LED71") (pin "2") (pinfunction "GND_2") (pintype "power_in"))
      (node (ref "LED72") (pin "2") (pinfunction "GND_2") (pintype "power_in"))
      (node (ref "LED73") (pin "2") (pinfunction "GND_2") (pintype "power_in"))
      (node (ref "LED74") (pin "2") (pinfunction "GND_2") (pintype "power_in"))
      (node (ref "LED75") (pin "2") (pinfunction "GND_2") (pintype "power_in"))
      (node (ref "LED76") (pin "2") (pinfunction "GND_2") (pintype "power_in"))
      (node (ref "LED77") (pin "2") (pinfunction "GND_2") (pintype "power_in"))
      (node (ref "LED78") (pin "2") (pinfunction "GND_2") (pintype "power_in"))
      (node (ref "LED79") (pin "2") (pinfunction "GND_2") (pintype "power_in"))
      (node (ref "LED8") (pin "2") (pinfunction "GND_2") (pintype "power_in"))
      (node (ref "LED80") (pin "2") (pinfunction "GND_2") (pintype "power_in"))
      (node (ref "LED9") (pin "2") (pinfunction "GND_2") (pintype "power_in"))
    )
    (net (code "6") (name "Net-(LED1-DO)") (class "Default")
      (node (ref "LED1") (pin "1") (pinfunction "DO_1") (pintype "output"))
      (node (ref "LED2") (pin "3") (pinfunction "DI_3") (pintype "input"))
    )
    (net (code "7") (name "Net-(LED2-DO)") (class "Default")
      (node (ref "LED2") (pin "1") (pinfunction "DO_1") (pintype "output"))
      (node (ref "LED3") (pin "3") (pinfunction "DI_3") (pintype "input"))
    )
    (net (code "8") (name "Net-(LED3-DO)") (class "Default")
      (node (ref "LED3") (pin "1") (pinfunction "DO_1") (pintype "output"))
      (node (ref "LED4") (pin "3") (pinfunction "DI_3") (pintype "input"))
    )
    (net (code "9") (name "Net-(LED4-DO)") (class "Default")
      (node (ref "LED4") (pin "1") (pinfunction "DO_1") (pintype "output"))
      (node (ref "LED5") (pin "3") (pinfunction "DI_3") (pintype "input"))
    )
    (net (code "10") (name "Net-(LED5-DO)") (class "Default")
      (node (ref "LED5") (pin "1") (pinfunction "DO_1") (pintype "output"))
      (node (ref "LED6") (pin "3") (pinfunction "DI_3") (pintype "input"))
    )
    (net (code "11") (name "Net-(LED6-DO)") (class "Default")
      (node (ref "LED6") (pin "1") (pinfunction "DO_1") (pintype "output"))
      (node (ref "LED7") (pin "3") (pinfunction "DI_3") (pintype "input"))
    )
    (net (code "12") (name "Net-(LED7-DO)") (class "Default")
      (node (ref "LED7") (pin "1") (pinfunction "DO_1") (pintype "output"))
      (node (ref "LED8") (pin "3") (pinfunction "DI_3") (pintype "input"))
    )
    (net (code "13") (name "Net-(LED8-DO)") (class "Default")
      (node (ref "LED8") (pin "1") (pinfunction "DO_1") (pintype "output"))
      (node (ref "LED9") (pin "3") (pinfunction "DI_3") (pintype "input"))
    )
    (net (code "14") (name "Net-(LED10-DI)") (class "Default")
      (node (ref "LED10") (pin "3") (pinfunction "DI_3") (pintype "input"))
      (node (ref "LED9") (pin "1") (pinfunction "DO_1") (pintype "output"))
    )
    (net (code "15") (name "Net-(LED10-DO)") (class "Default")
      (node (ref "LED10") (pin "1") (pinfunction "DO_1") (pintype "output"))
      (node (ref "LED11") (pin "3") (pinfunction "DI_3") (pintype "input"))
    )
    (net (code "16") (name "Net-(LED11-DO)") (class "Default")
      (node (ref "LED11") (pin "1") (pinfunction "DO_1") (pintype "output"))
      (node (ref "LED12") (pin "3") (pinfunction "DI_3") (pintype "input"))
    )
    (net (code "17") (name "Net-(LED12-DO)") (class "Default")
      (node (ref "LED12") (pin "1") (pinfunction "DO_1") (pintype "output"))
      (node (ref "LED13") (pin "3") (pinfunction "DI_3") (pintype "input"))
    )
    (net (code "18") (name "Net-(LED13-DO)") (class "Default")
      (node (ref "LED13") (pin "1") (pinfunction "DO_1") (pintype "output"))
      (node (ref "LED14") (pin "3") (pinfunction "DI_3") (pintype "input"))
    )
    (net (code "19") (name "Net-(LED14-DO)") (class "Default")
      (node (ref "LED14") (pin "1") (pinfunction "DO_1") (pintype "output"))
      (node (ref "LED15") (pin "3") (pinfunction "DI_3") (pintype "input"))
    )
    (net (code "20") (name "Net-(LED15-DO)") (class "Default")
      (node (ref "LED15") (pin "1") (pinfunction "DO_1") (pintype "output"))
      (node (ref "LED16") (pin "3") (pinfunction "DI_3") (pintype "input"))
    )
    (net (code "21") (name "Net-(LED16-DO)") (class "Default")
      (node (ref "LED16") (pin "1") (pinfunction "DO_1") (pintype "output"))
      (node (ref "LED17") (pin "3") (pinfunction "DI_3") (pintype "input"))
    )
    (net (code "22") (name "Net-(LED17-DO)") (class "Default")
      (node (ref "LED17") (pin "1") (pinfunction "DO_1") (pintype "output"))
      (node (ref "LED18") (pin "3") (pinfunction "DI_3") (pintype "input"))
    )
    (net (code "23") (name "Net-(LED18-DO)") (class "Default")
      (node (ref "LED18") (pin "1") (pinfunction "DO_1") (pintype "output"))
      (node (ref "LED19") (pin "3") (pinfunction "DI_3") (pintype "input"))
    )
    (net (code "24") (name "Net-(LED19-DO)") (class "Default")
      (node (ref "LED19") (pin "1") (pinfunction "DO_1") (pintype "output"))
      (node (ref "LED20") (pin "3") (pinfunction "DI_3") (pintype "input"))
    )
    (net (code "25") (name "Net-(LED20-DO)") (class "Default")
      (node (ref "LED20") (pin "1") (pinfunction "DO_1") (pintype "output"))
      (node (ref "LED21") (pin "3") (pinfunction "DI_3") (pintype "input"))
    )
    (net (code "26") (name "Net-(LED21-DO)") (class "Default")
      (node (ref "LED21") (pin "1") (pinfunction "DO_1") (pintype "output"))
      (node (ref "LED22") (pin "3") (pinfunction "DI_3") (pintype "input"))
    )
    (net (code "27") (name "Net-(LED22-DO)") (class "Default")
      (node (ref "LED22") (pin "1") (pinfunction "DO_1") (pintype "output"))
      (node (ref "LED23") (pin "3") (pinfunction "DI_3") (pintype "input"))
    )
    (net (code "28") (name "Net-(LED23-DO)") (class "Default")
      (node (ref "LED23") (pin "1") (pinfunction "DO_1") (pintype "output"))
      (node (ref "LED24") (pin "3") (pinfunction "DI_3") (pintype "input"))
    )
    (net (code "29") (name "Net-(LED24-DO)") (class "Default")
      (node (ref "LED24") (pin "1") (pinfunction "DO_1") (pintype "output"))
      (node (ref "LED25") (pin "3") (pinfunction "DI_3") (pintype "input"))
    )
    (net (code "30") (name "Net-(LED25-DO)") (class "Default")
      (node (ref "LED25") (pin "1") (pinfunction "DO_1") (pintype "output"))
      (node (ref "LED26") (pin "3") (pinfunction "DI_3") (pintype "input"))
    )
    (net (code "31") (name "Net-(LED26-DO)") (class "Default")
      (node (ref "LED26") (pin "1") (pinfunction "DO_1") (pintype "output"))
      (node (ref "LED27") (pin "3") (pinfunction "DI_3") (pintype "input"))
    )
    (net (code "32") (name "Net-(LED27-DO)") (class "Default")
      (node (ref "LED27") (pin "1") (pinfunction "DO_1") (pintype "output"))
      (node (ref "LED28") (pin "3") (pinfunction "DI_3") (pintype "input"))
    )
    (net (code "33") (name "Net-(LED28-DO)") (class "Default")
      (node (ref "LED28") (pin "1") (pinfunction "DO_1") (pintype "output"))
      (node (ref "LED29") (pin "3") (pinfunction "DI_3") (pintype "input"))
    )
    (net (code "34") (name "Net-(LED29-DO)") (class "Default")
      (node (ref "LED29") (pin "1") (pinfunction "DO_1") (pintype "output"))
      (node (ref "LED30") (pin "3") (pinfunction "DI_3") (pintype "input"))
    )
    (net (code "35") (name "Net-(LED30-DO)") (class "Default")
      (node (ref "LED30") (pin "1") (pinfunction "DO_1") (pintype "output"))
      (node (ref "LED31") (pin "3") (pinfunction "DI_3") (pintype "input"))
    )
    (net (code "36") (name "Net-(LED31-DO)") (class "Default")
      (node (ref "LED31") (pin "1") (pinfunction "DO_1") (pintype "output"))
      (node (ref "LED32") (pin "3") (pinfunction "DI_3") (pintype "input"))
    )
    (net (code "37") (name "Net-(LED32-DO)") (class "Default")
      (node (ref "LED32") (pin "1") (pinfunction "DO_1") (pintype "output"))
      (node (ref "LED33") (pin "3") (pinfunction "DI_3") (pintype "input"))
    )
    (net (code "38") (name "Net-(LED33-DO)") (class "Default")
      (node (ref "LED33") (pin "1") (pinfunction "DO_1") (pintype "output"))
      (node (ref "LED34") (pin "3") (pinfunction "DI_3") (pintype "input"))
    )
    (net (code "39") (name "Net-(LED34-DO)") (class "Default")
      (node (ref "LED34") (pin "1") (pinfunction "DO_1") (pintype "output"))
      (node (ref "LED35") (pin "3") (pinfunction "DI_3") (pintype "input"))
    )
    (net (code "40") (name "Net-(LED35-DO)") (class "Default")
      (node (ref "LED35") (pin "1") (pinfunction "DO_1") (pintype "output"))
      (node (ref "LED36") (pin "3") (pinfunction "DI_3") (pintype "input"))
    )
    (net (code "41") (name "Net-(LED36-DO)") (class "Default")
      (node (ref "LED36") (pin "1") (pinfunction "DO_1") (pintype "output"))
      (node (ref "LED37") (pin "3") (pinfunction "DI_3") (pintype "input"))
    )
    (net (code "42") (name "Net-(LED37-DO)") (class "Default")
      (node (ref "LED37") (pin "1") (pinfunction "DO_1") (pintype "output"))
      (node (ref "LED38") (pin "3") (pinfunction "DI_3") (pintype "input"))
    )
    (net (code "43") (name "Net-(LED38-DO)") (class "Default")
      (node (ref "LED38") (pin "1") (pinfunction "DO_1") (pintype "output"))
      (node (ref "LED39") (pin "3") (pinfunction "DI_3") (pintype "input"))
    )
    (net (code "44") (name "Net-(LED39-DO)") (class "Default")
      (node (ref "LED39") (pin "1") (pinfunction "DO_1") (pintype "output"))
      (node (ref "LED40") (pin "3") (pinfunction "DI_3") (pintype "input"))
    )
    (net (code "45") (name "Net-(LED41-DO)") (class "Default")
      (node (ref "LED41") (pin "1") (pinfunction "DO_1") (pintype "output"))
      (node (ref "LED42") (pin "3") (pinfunction "DI_3") (pintype "input"))
    )
    (net (code "46") (name "Net-(LED42-DO)") (class "Default")
      (node (ref "LED42") (pin "1") (pinfunction "DO_1") (pintype "output"))
      (node (ref "LED43") (pin "3") (pinfunction "DI_3") (pintype "input"))
    )
    (net (code "47") (name "Net-(LED43-DO)") (class "Default")
      (node (ref "LED43") (pin "1") (pinfunction "DO_1") (pintype "output"))
      (node (ref "LED44") (pin "3") (pinfunction "DI_3") (pintype "input"))
    )
    (net (code "48") (name "Net-(LED44-DO)") (class "Default")
      (node (ref "LED44") (pin "1") (pinfunction "DO_1") (pintype "output"))
      (node (ref "LED45") (pin "3") (pinfunction "DI_3") (pintype "input"))
    )
    (net (code "49") (name "Net-(LED45-DO)") (class "Default")
      (node (ref "LED45") (pin "1") (pinfunction "DO_1") (pintype "output"))
      (node (ref "LED46") (pin "3") (pinfunction "DI_3") (pintype "input"))
    )
    (net (code "50") (name "Net-(LED46-DO)") (class "Default")
      (node (ref "LED46") (pin "1") (pinfunction "DO_1") (pintype "output"))
      (node (ref "LED47") (pin "3") (pinfunction "DI_3") (pintype "input"))
    )
    (net (code "51") (name "Net-(LED47-DO)") (class "Default")
      (node (ref "LED47") (pin "1") (pinfunction "DO_1") (pintype "output"))
      (node (ref "LED48") (pin "3") (pinfunction "DI_3") (pintype "input"))
    )
    (net (code "52") (name "Net-(LED48-DO)") (class "Default")
      (node (ref "LED48") (pin "1") (pinfunction "DO_1") (pintype "output"))
      (node (ref "LED49") (pin "3") (pinfunction "DI_3") (pintype "input"))
    )
    (net (code "53") (name "Net-(LED49-DO)") (class "Default")
      (node (ref "LED49") (pin "1") (pinfunction "DO_1") (pintype "output"))
      (node (ref "LED50") (pin "3") (pinfunction "DI_3") (pintype "input"))
    )
    (net (code "54") (name "Net-(LED50-DO)") (class "Default")
      (node (ref "LED50") (pin "1") (pinfunction "DO_1") (pintype "output"))
      (node (ref "LED51") (pin "3") (pinfunction "DI_3") (pintype "input"))
    )
    (net (code "55") (name "Net-(LED51-DO)") (class "Default")
      (node (ref "LED51") (pin "1") (pinfunction "DO_1") (pintype "output"))
      (node (ref "LED52") (pin "3") (pinfunction "DI_3") (pintype "input"))
    )
    (net (code "56") (name "Net-(LED52-DO)") (class "Default")
      (node (ref "LED52") (pin "1") (pinfunction "DO_1") (pintype "output"))
      (node (ref "LED53") (pin "3") (pinfunction "DI_3") (pintype "input"))
    )
    (net (code "57") (name "Net-(LED53-DO)") (class "Default")
      (node (ref "LED53") (pin "1") (pinfunction "DO_1") (pintype "output"))
      (node (ref "LED54") (pin "3") (pinfunction "DI_3") (pintype "input"))
    )
    (net (code "58") (name "Net-(LED54-DO)") (class "Default")
      (node (ref "LED54") (pin "1") (pinfunction "DO_1") (pintype "output"))
      (node (ref "LED55") (pin "3") (pinfunction "DI_3") (pintype "input"))
    )
    (net (code "59") (name "Net-(LED55-DO)") (class "Default")
      (node (ref "LED55") (pin "1") (pinfunction "DO_1") (pintype "output"))
      (node (ref "LED56") (pin "3") (pinfunction "DI_3") (pintype "input"))
    )
    (net (code "60") (name "Net-(LED56-DO)") (class "Default")
      (node (ref "LED56") (pin "1") (pinfunction "DO_1") (pintype "output"))
      (node (ref "LED57") (pin "3") (pinfunction "DI_3") (pintype "input"))
    )
    (net (code "61") (name "Net-(LED57-DO)") (class "Default")
      (node (ref "LED57") (pin "1") (pinfunction "DO_1") (pintype "output"))
      (node (ref "LED58") (pin "3") (pinfunction "DI_3") (pintype "input"))
    )
    (net (code "62") (name "Net-(LED58-DO)") (class "Default")
      (node (ref "LED58") (pin "1") (pinfunction "DO_1") (pintype "output"))
      (node (ref "LED59") (pin "3") (pinfunction "DI_3") (pintype "input"))
    )
    (net (code "63") (name "Net-(LED59-DO)") (class "Default")
      (node (ref "LED59") (pin "1") (pinfunction "DO_1") (pintype "output"))
      (node (ref "LED60") (pin "3") (pinfunction "DI_3") (pintype "input"))
    )
    (net (code "64") (name "Net-(LED60-DO)") (class "Default")
      (node (ref "LED60") (pin "1") (pinfunction "DO_1") (pintype "output"))
      (node (ref "LED61") (pin "3") (pinfunction "DI_3") (pintype "input"))
    )
    (net (code "65") (name "Net-(LED61-DO)") (class "Default")
      (node (ref "LED61") (pin "1") (pinfunction "DO_1") (pintype "output"))
      (node (ref "LED62") (pin "3") (pinfunction "DI_3") (pintype "input"))
    )
    (net (code "66") (name "Net-(LED62-DO)") (class "Default")
      (node (ref "LED62") (pin "1") (pinfunction "DO_1") (pintype "output"))
      (node (ref "LED63") (pin "3") (pinfunction "DI_3") (pintype "input"))
    )
    (net (code "67") (name "Net-(LED63-DO)") (class "Default")
      (node (ref "LED63") (pin "1") (pinfunction "DO_1") (pintype "output"))
      (node (ref "LED64") (pin "3") (pinfunction "DI_3") (pintype "input"))
    )
    (net (code "68") (name "Net-(LED64-DO)") (class "Default")
      (node (ref "LED64") (pin "1") (pinfunction "DO_1") (pintype "output"))
      (node (ref "LED65") (pin "3") (pinfunction "DI_3") (pintype "input"))
    )
    (net (code "69") (name "Net-(LED65-DO)") (class "Default")
      (node (ref "LED65") (pin "1") (pinfunction "DO_1") (pintype "output"))
      (node (ref "LED66") (pin "3") (pinfunction "DI_3") (pintype "input"))
    )
    (net (code "70") (name "Net-(LED66-DO)") (class "Default")
      (node (ref "LED66") (pin "1") (pinfunction "DO_1") (pintype "output"))
      (node (ref "LED67") (pin "3") (pinfunction "DI_3") (pintype "input"))
    )
    (net (code "71") (name "Net-(LED67-DO)") (class "Default")
      (node (ref "LED67") (pin "1") (pinfunction "DO_1") (pintype "output"))
      (node (ref "LED68") (pin "3") (pinfunction "DI_3") (pintype "input"))
    )
    (net (code "72") (name "Net-(LED68-DO)") (class "Default")
      (node (ref "LED68") (pin "1") (pinfunction "DO_1") (pintype "output"))
      (node (ref "LED69") (pin "3") (pinfunction "DI_3") (pintype "input"))
    )
    (net (code "73") (name "Net-(LED69-DO)") (class "Default")
      (node (ref "LED69") (pin "1") (pinfunction "DO_1") (pintype "output"))
      (node (ref "LED70") (pin "3") (pinfunction "DI_3") (pintype "input"))
    )
    (net (code "74") (name "Net-(LED70-DO)") (class "Default")
      (node (ref "LED70") (pin "1") (pinfunction "DO_1") (pintype "output"))
      (node (ref "LED71") (pin "3") (pinfunction "DI_3") (pintype "input"))
    )
    (net (code "75") (name "Net-(LED71-DO)") (class "Default")
      (node (ref "LED71") (pin "1") (pinfunction "DO_1") (pintype "output"))
      (node (ref "LED72") (pin "3") (pinfunction "DI_3") (pintype "input"))
    )
    (net (code "76") (name "Net-(LED72-DO)") (class "Default")
      (node (ref "LED72") (pin "1") (pinfunction "DO_1") (pintype "output"))
      (node (ref "LED73") (pin "3") (pinfunction "DI_3") (pintype "input"))
    )
    (net (code "77") (name "Net-(LED73-DO)") (class "Default")
      (node (ref "LED73") (pin "1") (pinfunction "DO_1") (pintype "output"))
      (node (ref "LED74") (pin "3") (pinfunction "DI_3") (pintype "input"))
    )
    (net (code "78") (name "Net-(LED74-DO)") (class "Default")
      (node (ref "LED74") (pin "1") (pinfunction "DO_1") (pintype "output"))
      (node (ref "LED75") (pin "3") (pinfunction "DI_3") (pintype "input"))
    )
    (net (code "79") (name "Net-(LED75-DO)") (class "Default")
      (node (ref "LED75") (pin "1") (pinfunction "DO_1") (pintype "output"))
      (node (ref "LED76") (pin "3") (pinfunction "DI_3") (pintype "input"))
    )
    (net (code "80") (name "Net-(LED76-DO)") (class "Default")
      (node (ref "LED76") (pin "1") (pinfunction "DO_1") (pintype "output"))
      (node (ref "LED77") (pin "3") (pinfunction "DI_3") (pintype "input"))
    )
    (net (code "81") (name "Net-(LED77-DO)") (class "Default")
      (node (ref "LED77") (pin "1") (pinfunction "DO_1") (pintype "output"))
      (node (ref "LED78") (pin "3") (pinfunction "DI_3") (pintype "input"))
    )
    (net (code "82") (name "Net-(LED78-DO)") (class "Default")
      (node (ref "LED78") (pin "1") (pinfunction "DO_1") (pintype "output"))
      (node (ref "LED79") (pin "3") (pinfunction "DI_3") (pintype "input"))
    )
    (net (code "83") (name "Net-(LED79-DO)") (class "Default")
      (node (ref "LED79") (pin "1") (pinfunction "DO_1") (pintype "output"))
      (node (ref "LED80") (pin "3") (pinfunction "DI_3") (pintype "input"))
    )
    (net (code "84") (name "unconnected-(J1-Pad4)") (class "Default")
      (node (ref "J1") (pin "4") (pinfunction "4_4") (pintype "passive"))
    )
    (net (code "85") (name "unconnected-(J4-Pad4)") (class "Default")
      (node (ref "J4") (pin "4") (pinfunction "4_4") (pintype "passive"))
    )
  )
)
